# IO.net
KiCad netlist of a schematic drawn in Altium Designer
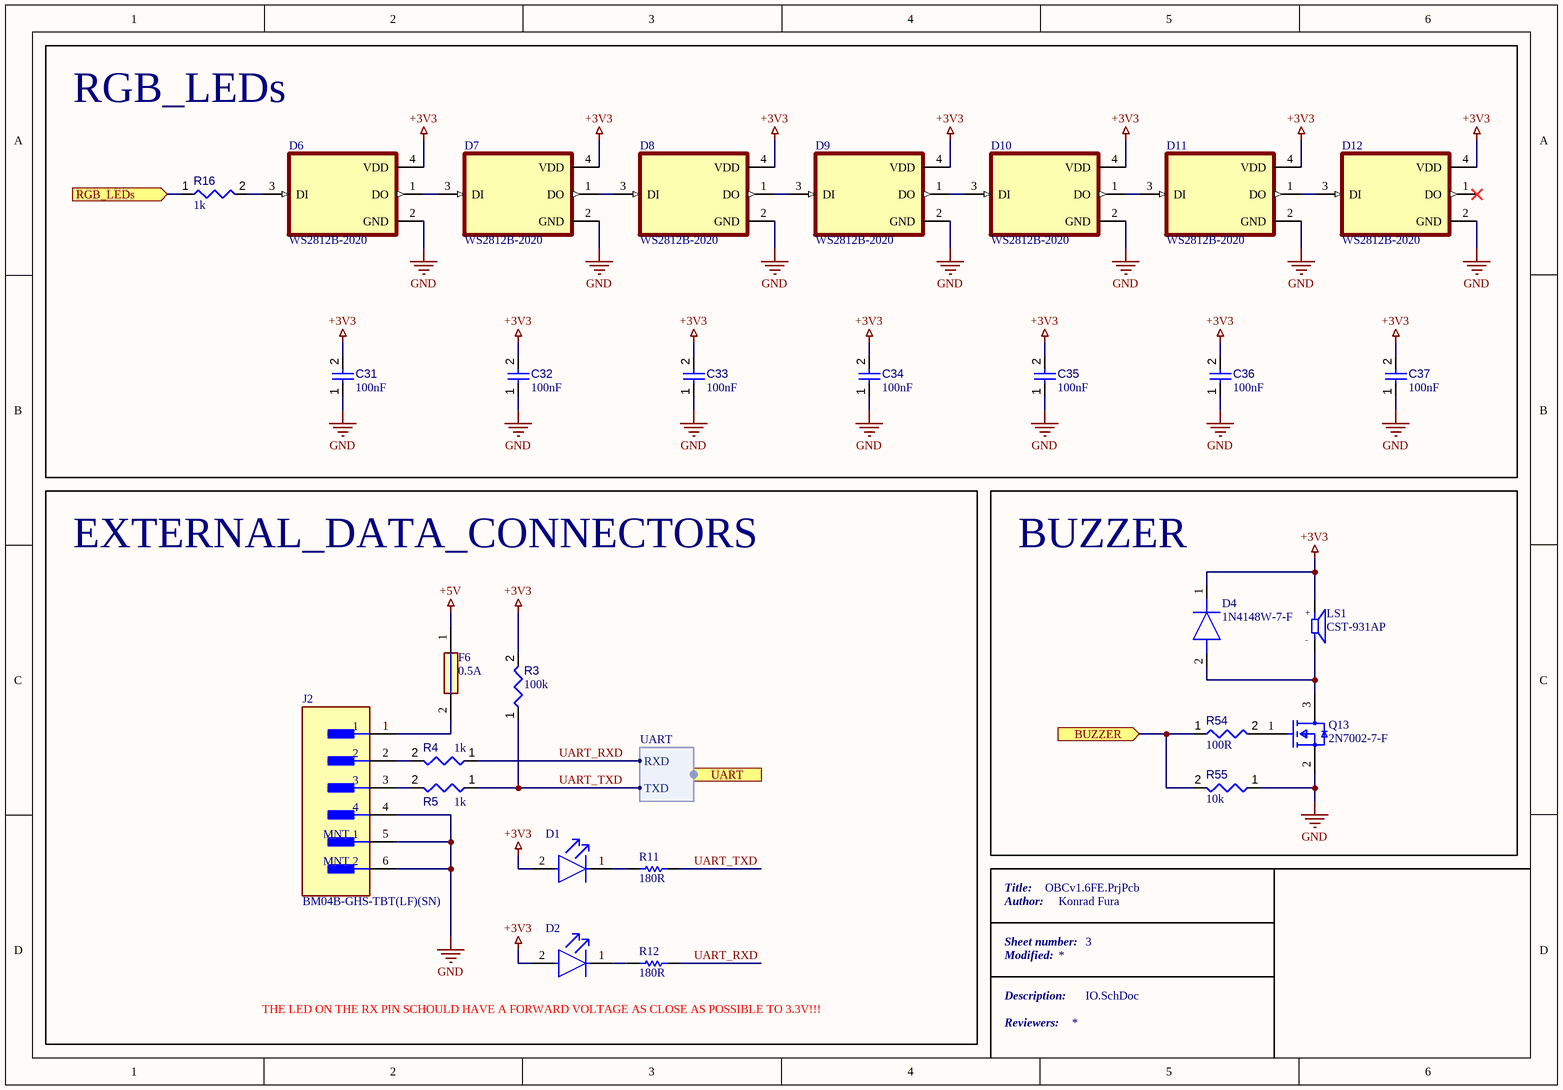
[diagram p0: IO.SchDoc]

(export (version "E")
  (design (tool "Eeschema 10.0.6"))
  (components
    (comp (ref "C31")
      (value "100nF")
      (footprint "CAPC0402(1005)60_L")
      (description "Chip Capacitor, 100nF +/-20%, 10V, 0402, Thickness 0.6 mm")
      (fields (field (name "TOLERANCE") "20%") (field (name "Comment") "Capacitor 100nF +/-20% 10V 0402"))
      (libsource (lib "PWr in Space team") (part "CAP-NP-2"))
    )
    (comp (ref "C32")
      (value "100nF")
      (footprint "CAPC0402(1005)60_L")
      (description "Chip Capacitor, 100nF +/-20%, 10V, 0402, Thickness 0.6 mm")
      (fields (field (name "TOLERANCE") "20%") (field (name "Comment") "Capacitor 100nF +/-20% 10V 0402"))
      (libsource (lib "PWr in Space team") (part "CAP-NP-2"))
    )
    (comp (ref "C33")
      (value "100nF")
      (footprint "CAPC0402(1005)60_L")
      (description "Chip Capacitor, 100nF +/-20%, 10V, 0402, Thickness 0.6 mm")
      (fields (field (name "TOLERANCE") "20%") (field (name "Comment") "Capacitor 100nF +/-20% 10V 0402"))
      (libsource (lib "PWr in Space team") (part "CAP-NP-2"))
    )
    (comp (ref "C34")
      (value "100nF")
      (footprint "CAPC0402(1005)60_L")
      (description "Chip Capacitor, 100nF +/-20%, 10V, 0402, Thickness 0.6 mm")
      (fields (field (name "TOLERANCE") "20%") (field (name "Comment") "Capacitor 100nF +/-20% 10V 0402"))
      (libsource (lib "PWr in Space team") (part "CAP-NP-2"))
    )
    (comp (ref "C35")
      (value "100nF")
      (footprint "CAPC0402(1005)60_L")
      (description "Chip Capacitor, 100nF +/-20%, 10V, 0402, Thickness 0.6 mm")
      (fields (field (name "TOLERANCE") "20%") (field (name "Comment") "Capacitor 100nF +/-20% 10V 0402"))
      (libsource (lib "PWr in Space team") (part "CAP-NP-2"))
    )
    (comp (ref "C36")
      (value "100nF")
      (footprint "CAPC0402(1005)60_L")
      (description "Chip Capacitor, 100nF +/-20%, 10V, 0402, Thickness 0.6 mm")
      (fields (field (name "TOLERANCE") "20%") (field (name "Comment") "Capacitor 100nF +/-20% 10V 0402"))
      (libsource (lib "PWr in Space team") (part "CAP-NP-2"))
    )
    (comp (ref "C37")
      (value "100nF")
      (footprint "CAPC0402(1005)60_L")
      (description "Chip Capacitor, 100nF +/-20%, 10V, 0402, Thickness 0.6 mm")
      (fields (field (name "TOLERANCE") "20%") (field (name "Comment") "Capacitor 100nF +/-20% 10V 0402"))
      (libsource (lib "PWr in Space team") (part "CAP-NP-2"))
    )
    (comp (ref "D1")
      (value "~")
      (footprint "FP-LTST-C191TBKT-MFG")
      (description "LED BLUE CLEAR CHIP SMD")
      (libsource (lib "Altium Content Vault") (part "8706943c75ba83719d021d2fdc84c58"))
    )
    (comp (ref "D2")
      (value "~")
      (footprint "FP-LTST-C191TBKT-MFG")
      (description "LED BLUE CLEAR CHIP SMD")
      (libsource (lib "Altium Content Vault") (part "8706943c75ba83719d021d2fdc84c58"))
    )
    (comp (ref "D4")
      (value "1N4148W-7-F")
      (footprint "SamacSys:SOD3716X145N")
      (description "Diode")
      (fields (field (name "MOUSER PART NUMBER") "621-1N4148W-F"))
      (libsource (lib "*") (part "1N4148W-7-F"))
    )
    (comp (ref "D6")
      (value "WS2812B-2020")
      (footprint "LED_WS2812-2020")
      (description "Intelligent control LED integrated light source")
      (fields (field (name "MP") "WS2812-2020") (field (name "MF") "{'manufacturer': u'Worldsemi'}"))
      (libsource (lib "SnapEDA_Library") (part "WS2812-2020"))
    )
    (comp (ref "D7")
      (value "WS2812B-2020")
      (footprint "LED_WS2812-2020")
      (description "Intelligent control LED integrated light source")
      (fields (field (name "MP") "WS2812-2020") (field (name "MF") "{'manufacturer': u'Worldsemi'}"))
      (libsource (lib "SnapEDA_Library") (part "WS2812-2020"))
    )
    (comp (ref "D8")
      (value "WS2812B-2020")
      (footprint "LED_WS2812-2020")
      (description "Intelligent control LED integrated light source")
      (fields (field (name "MP") "WS2812-2020") (field (name "MF") "{'manufacturer': u'Worldsemi'}"))
      (libsource (lib "SnapEDA_Library") (part "WS2812-2020"))
    )
    (comp (ref "D9")
      (value "WS2812B-2020")
      (footprint "LED_WS2812-2020")
      (description "Intelligent control LED integrated light source")
      (fields (field (name "MP") "WS2812-2020") (field (name "MF") "{'manufacturer': u'Worldsemi'}"))
      (libsource (lib "SnapEDA_Library") (part "WS2812-2020"))
    )
    (comp (ref "D10")
      (value "WS2812B-2020")
      (footprint "LED_WS2812-2020")
      (description "Intelligent control LED integrated light source")
      (fields (field (name "MP") "WS2812-2020") (field (name "MF") "{'manufacturer': u'Worldsemi'}"))
      (libsource (lib "SnapEDA_Library") (part "WS2812-2020"))
    )
    (comp (ref "D11")
      (value "WS2812B-2020")
      (footprint "LED_WS2812-2020")
      (description "Intelligent control LED integrated light source")
      (fields (field (name "MP") "WS2812-2020") (field (name "MF") "{'manufacturer': u'Worldsemi'}"))
      (libsource (lib "SnapEDA_Library") (part "WS2812-2020"))
    )
    (comp (ref "D12")
      (value "WS2812B-2020")
      (footprint "LED_WS2812-2020")
      (description "Intelligent control LED integrated light source")
      (fields (field (name "MP") "WS2812-2020") (field (name "MF") "{'manufacturer': u'Worldsemi'}"))
      (libsource (lib "SnapEDA_Library") (part "WS2812-2020"))
    )
    (comp (ref "F6")
      (value "0.5A")
      (footprint "SamacSys:FUSC2114X75N")
      (description "Fuse")
      (fields
        (field (name "MANUFACTURER_PART_NUMBER") "0805L020/24YR")
        (field (name "MOUSER PART NUMBER") "576-0805L020/24YR")
      )
      (libsource (lib "*") (part "0805L020_24YR"))
    )
    (comp (ref "J2")
      (value "BM04B-GHS-TBT(LF)(SN)")
      (footprint "FP-BM04B-GHS-TBT_LF_SN-MFG")
      (description "CONN HEADER SMD 4POS 1.25MM")
      (libsource (lib "Altium Content Vault") (part "8e3688c4b118bffc0dd9b7401e414ba"))
    )
    (comp (ref "LS1")
      (value "CST-931AP")
      (footprint "CST-931AP:CUI_CST-931AP")
      (description "9 mm, 3 V, 85 dB, Through Hole, Magnetic Audio Transducer Buzzer")
      (fields (field (name "MF") "{'manufacturer': u'CUI Devices'}"))
      (libsource (lib "CST-931AP") (part "CST-931AP"))
    )
    (comp (ref "Q13")
      (value "2N7002-7-F")
      (footprint "FP-SOT23-MFG")
      (description "MOSFET N-CH 60V 115MA SOT23-3")
      (fields (field (name "VOLTAGE") "60V"))
      (libsource (lib "Altium Content Vault") (part "3b9c635fedb024a5347a57b145af9cc"))
    )
    (comp (ref "R3")
      (value "100k")
      (footprint "RESC0402(1005)_L")
      (description "Chip Resistor, 100 kOhms, +/-1 %, 63 mW, -55 to 155 degC, 0402")
      (fields (field (name "TOLERANCE") "1%") (field (name "POWER") "63mW"))
      (libsource (lib "PWr in Space team") (part "RES-2"))
    )
    (comp (ref "R4")
      (value "1k")
      (footprint "RESC0402(1005)_L")
      (description "Chip Resistor, 1 kOhms, +/-5 %, 63 mW, -55 to 155 degC, 0402")
      (fields (field (name "TOLERANCE") "5%") (field (name "POWER") "63mW"))
      (libsource (lib "PWr in Space team") (part "RES-2"))
    )
    (comp (ref "R5")
      (value "1k")
      (footprint "RESC0402(1005)_L")
      (description "Chip Resistor, 1 kOhms, +/-5 %, 63 mW, -55 to 155 degC, 0402")
      (fields (field (name "TOLERANCE") "5%") (field (name "POWER") "63mW"))
      (libsource (lib "PWr in Space team") (part "RES-2"))
    )
    (comp (ref "R11")
      (value "180R")
      (footprint "RESC1005X40X25NL05T05")
      (fields (field (name "MANUFACTURER") "Panasonic") (field (name "PART NUMBER") "ERJ2RKF1800X"))
      (libsource (lib "Altium Content Vault") (part "RES"))
    )
    (comp (ref "R12")
      (value "180R")
      (footprint "RESC1005X40X25NL05T05")
      (fields (field (name "MANUFACTURER") "Panasonic") (field (name "PART NUMBER") "ERJ2RKF1800X"))
      (libsource (lib "Altium Content Vault") (part "RES"))
    )
    (comp (ref "R16")
      (value "1k")
      (footprint "RESC0402(1005)_L")
      (description "Chip Resistor, 1 kOhms, +/-5 %, 63 mW, -55 to 155 degC, 0402")
      (fields (field (name "TOLERANCE") "5%") (field (name "POWER") "63mW"))
      (libsource (lib "PWr in Space team") (part "RES-2"))
    )
    (comp (ref "R54")
      (value "100R")
      (footprint "RESC0402(1005)_L")
      (description "Chip Resistor, 100 Ohms, +/-1 %, 63 mW, -55 to 155 degC, 0402")
      (fields (field (name "POWER") "63mW") (field (name "TOLERANCE") "1%"))
      (libsource (lib "PWr in Space team") (part "RES-2"))
    )
    (comp (ref "R55")
      (value "10k")
      (footprint "RESC0402(1005)_L")
      (description "Chip Resistor, 10 kOhms, +/-1 %, 63 mW, -55 to 125 degC, 0402")
      (fields (field (name "POWER") "63mW") (field (name "TOLERANCE") "1%"))
      (libsource (lib "PWr in Space team") (part "RES-2"))
    )
  )
  (nets
    (net (code "2") (name "+3V3") (class "Default")
      (node (ref "C31") (pin "2") (pinfunction "2_2") (pintype "passive"))
      (node (ref "C32") (pin "2") (pinfunction "2_2") (pintype "passive"))
      (node (ref "C33") (pin "2") (pinfunction "2_2") (pintype "passive"))
      (node (ref "C34") (pin "2") (pinfunction "2_2") (pintype "passive"))
      (node (ref "C35") (pin "2") (pinfunction "2_2") (pintype "passive"))
      (node (ref "C36") (pin "2") (pinfunction "2_2") (pintype "passive"))
      (node (ref "C37") (pin "2") (pinfunction "2_2") (pintype "passive"))
      (node (ref "D1") (pin "2") (pinfunction "A_2") (pintype "passive"))
      (node (ref "D10") (pin "4") (pinfunction "VDD_4") (pintype "power_in"))
      (node (ref "D11") (pin "4") (pinfunction "VDD_4") (pintype "power_in"))
      (node (ref "D12") (pin "4") (pinfunction "VDD_4") (pintype "power_in"))
      (node (ref "D2") (pin "2") (pinfunction "A_2") (pintype "passive"))
      (node (ref "D4") (pin "1") (pinfunction "K_1") (pintype "passive"))
      (node (ref "D6") (pin "4") (pinfunction "VDD_4") (pintype "power_in"))
      (node (ref "D7") (pin "4") (pinfunction "VDD_4") (pintype "power_in"))
      (node (ref "D8") (pin "4") (pinfunction "VDD_4") (pintype "power_in"))
      (node (ref "D9") (pin "4") (pinfunction "VDD_4") (pintype "power_in"))
      (node (ref "LS1") (pin "P") (pinfunction "P_P") (pintype "passive"))
      (node (ref "R3") (pin "2") (pinfunction "2_2") (pintype "passive"))
    )
    (net (code "3") (name "+5V") (class "Default")
      (node (ref "F6") (pin "1") (pinfunction "1_1") (pintype "passive"))
    )
    (net (code "4") (name "/BUZZER") (class "Default")
      (node (ref "R54") (pin "1") (pinfunction "1_1") (pintype "passive"))
      (node (ref "R55") (pin "2") (pinfunction "2_2") (pintype "passive"))
    )
    (net (code "5") (name "/RGB_LEDs") (class "Default")
      (node (ref "R16") (pin "1") (pinfunction "1_1") (pintype "passive"))
    )
    (net (code "6") (name "/UART_RXD") (class "Default")
      (node (ref "R12") (pin "2") (pinfunction "2_2") (pintype "passive"))
      (node (ref "R4") (pin "1") (pinfunction "1_1") (pintype "passive"))
    )
    (net (code "7") (name "/UART_TXD") (class "Default")
      (node (ref "R11") (pin "2") (pinfunction "2_2") (pintype "passive"))
      (node (ref "R3") (pin "1") (pinfunction "1_1") (pintype "passive"))
      (node (ref "R5") (pin "1") (pinfunction "1_1") (pintype "passive"))
    )
    (net (code "9") (name "GND") (class "Default")
      (node (ref "C31") (pin "1") (pinfunction "1_1") (pintype "passive"))
      (node (ref "C32") (pin "1") (pinfunction "1_1") (pintype "passive"))
      (node (ref "C33") (pin "1") (pinfunction "1_1") (pintype "passive"))
      (node (ref "C34") (pin "1") (pinfunction "1_1") (pintype "passive"))
      (node (ref "C35") (pin "1") (pinfunction "1_1") (pintype "passive"))
      (node (ref "C36") (pin "1") (pinfunction "1_1") (pintype "passive"))
      (node (ref "C37") (pin "1") (pinfunction "1_1") (pintype "passive"))
      (node (ref "D10") (pin "2") (pinfunction "GND_2") (pintype "power_in"))
      (node (ref "D11") (pin "2") (pinfunction "GND_2") (pintype "power_in"))
      (node (ref "D12") (pin "2") (pinfunction "GND_2") (pintype "power_in"))
      (node (ref "D6") (pin "2") (pinfunction "GND_2") (pintype "power_in"))
      (node (ref "D7") (pin "2") (pinfunction "GND_2") (pintype "power_in"))
      (node (ref "D8") (pin "2") (pinfunction "GND_2") (pintype "power_in"))
      (node (ref "D9") (pin "2") (pinfunction "GND_2") (pintype "power_in"))
      (node (ref "J2") (pin "4") (pinfunction "4_4") (pintype "passive"))
      (node (ref "J2") (pin "5") (pinfunction "MNT_1_5") (pintype "passive"))
      (node (ref "J2") (pin "6") (pinfunction "MNT_2_6") (pintype "passive"))
      (node (ref "Q13") (pin "2") (pinfunction "S_2") (pintype "passive"))
      (node (ref "R55") (pin "1") (pinfunction "1_1") (pintype "passive"))
    )
    (net (code "10") (name "Net-(D1-C)") (class "Default")
      (node (ref "D1") (pin "1") (pinfunction "C_1") (pintype "passive"))
      (node (ref "R11") (pin "1") (pinfunction "1_1") (pintype "passive"))
    )
    (net (code "11") (name "Net-(D2-C)") (class "Default")
      (node (ref "D2") (pin "1") (pinfunction "C_1") (pintype "passive"))
      (node (ref "R12") (pin "1") (pinfunction "1_1") (pintype "passive"))
    )
    (net (code "12") (name "Net-(D4-A)") (class "Default")
      (node (ref "D4") (pin "2") (pinfunction "A_2") (pintype "passive"))
      (node (ref "LS1") (pin "M") (pinfunction "M_M") (pintype "passive"))
      (node (ref "Q13") (pin "3") (pinfunction "D_3") (pintype "passive"))
    )
    (net (code "13") (name "Net-(D6-DI)") (class "Default")
      (node (ref "D6") (pin "3") (pinfunction "DI_3") (pintype "input"))
      (node (ref "R16") (pin "2") (pinfunction "2_2") (pintype "passive"))
    )
    (net (code "14") (name "Net-(D6-DO)") (class "Default")
      (node (ref "D6") (pin "1") (pinfunction "DO_1") (pintype "output"))
      (node (ref "D7") (pin "3") (pinfunction "DI_3") (pintype "input"))
    )
    (net (code "15") (name "Net-(D7-DO)") (class "Default")
      (node (ref "D7") (pin "1") (pinfunction "DO_1") (pintype "output"))
      (node (ref "D8") (pin "3") (pinfunction "DI_3") (pintype "input"))
    )
    (net (code "16") (name "Net-(D8-DO)") (class "Default")
      (node (ref "D8") (pin "1") (pinfunction "DO_1") (pintype "output"))
      (node (ref "D9") (pin "3") (pinfunction "DI_3") (pintype "input"))
    )
    (net (code "17") (name "Net-(D10-DI)") (class "Default")
      (node (ref "D10") (pin "3") (pinfunction "DI_3") (pintype "input"))
      (node (ref "D9") (pin "1") (pinfunction "DO_1") (pintype "output"))
    )
    (net (code "18") (name "Net-(D10-DO)") (class "Default")
      (node (ref "D10") (pin "1") (pinfunction "DO_1") (pintype "output"))
      (node (ref "D11") (pin "3") (pinfunction "DI_3") (pintype "input"))
    )
    (net (code "19") (name "Net-(D11-DO)") (class "Default")
      (node (ref "D11") (pin "1") (pinfunction "DO_1") (pintype "output"))
      (node (ref "D12") (pin "3") (pinfunction "DI_3") (pintype "input"))
    )
    (net (code "20") (name "Net-(F6-Pad2)") (class "Default")
      (node (ref "F6") (pin "2") (pinfunction "2_2") (pintype "passive"))
      (node (ref "J2") (pin "1") (pinfunction "1_1") (pintype "passive"))
    )
    (net (code "21") (name "Net-(J2-Pad2)") (class "Default")
      (node (ref "J2") (pin "2") (pinfunction "2_2") (pintype "passive"))
      (node (ref "R4") (pin "2") (pinfunction "2_2") (pintype "passive"))
    )
    (net (code "22") (name "Net-(J2-Pad3)") (class "Default")
      (node (ref "J2") (pin "3") (pinfunction "3_3") (pintype "passive"))
      (node (ref "R5") (pin "2") (pinfunction "2_2") (pintype "passive"))
    )
    (net (code "23") (name "Net-(Q13-G)") (class "Default")
      (node (ref "Q13") (pin "1") (pinfunction "G_1") (pintype "passive"))
      (node (ref "R54") (pin "2") (pinfunction "2_2") (pintype "passive"))
    )
    (net (code "24") (name "unconnected-(D12-DO-Pad1)") (class "Default")
      (node (ref "D12") (pin "1") (pinfunction "DO_1") (pintype "output+no_connect"))
    )
  )
)
